# CONNECTOR.net
KiCad netlist of a schematic drawn in Altium Designer
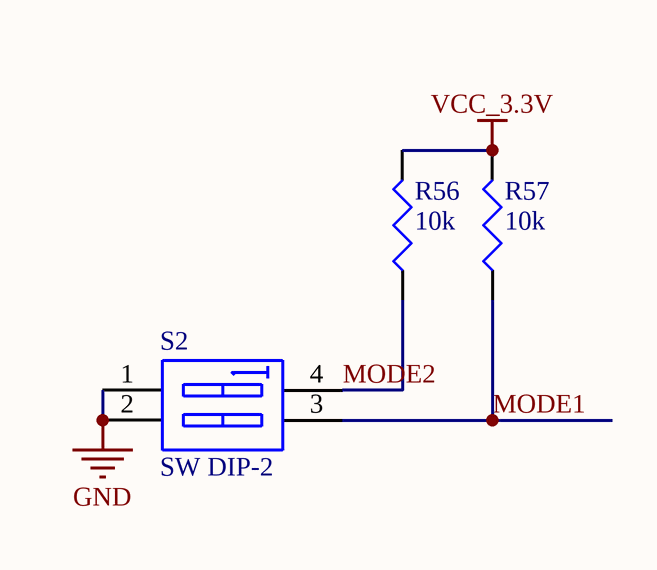
[diagram p0: CONNECTOR.SchDoc]

(export (version "E")
  (design (tool "Eeschema 10.0.6"))
  (components
    (comp (ref "R56")
      (value "10k")
      (footprint "0603R")
      (libsource (lib "ZWLIntegrated_Library") (part "RES1"))
    )
    (comp (ref "R57")
      (value "10k")
      (footprint "0603R")
      (libsource (lib "ZWLIntegrated_Library") (part "RES1"))
    )
    (comp (ref "S2")
      (value "SW DIP-2")
      (footprint "SW_SMT_4")
      (description "DIP Switch, 2 Position, SPST")
      (fields (field (name "PUBLISHER") "Altium Limited"))
      (libsource (lib "Miscellaneous Devices") (part "SW DIP-2"))
    )
  )
  (nets
    (net (code "1") (name "/MODE1") (class "Default")
      (node (ref "R57") (pin "1") (pinfunction "1_1") (pintype "passive"))
      (node (ref "S2") (pin "3") (pinfunction "B2_3") (pintype "passive"))
    )
    (net (code "2") (name "/MODE2") (class "Default")
      (node (ref "R56") (pin "1") (pinfunction "1_1") (pintype "passive"))
      (node (ref "S2") (pin "4") (pinfunction "B1_4") (pintype "passive"))
    )
    (net (code "3") (name "GND") (class "Default")
      (node (ref "S2") (pin "1") (pinfunction "A1_1") (pintype "passive"))
      (node (ref "S2") (pin "2") (pinfunction "A2_2") (pintype "passive"))
    )
    (net (code "4") (name "VCC_3.3V") (class "Default")
      (node (ref "R56") (pin "2") (pinfunction "2_2") (pintype "passive"))
      (node (ref "R57") (pin "2") (pinfunction "2_2") (pintype "passive"))
    )
  )
)
